# ADC_AK5572.net
KiCad netlist of a schematic drawn in Altium Designer
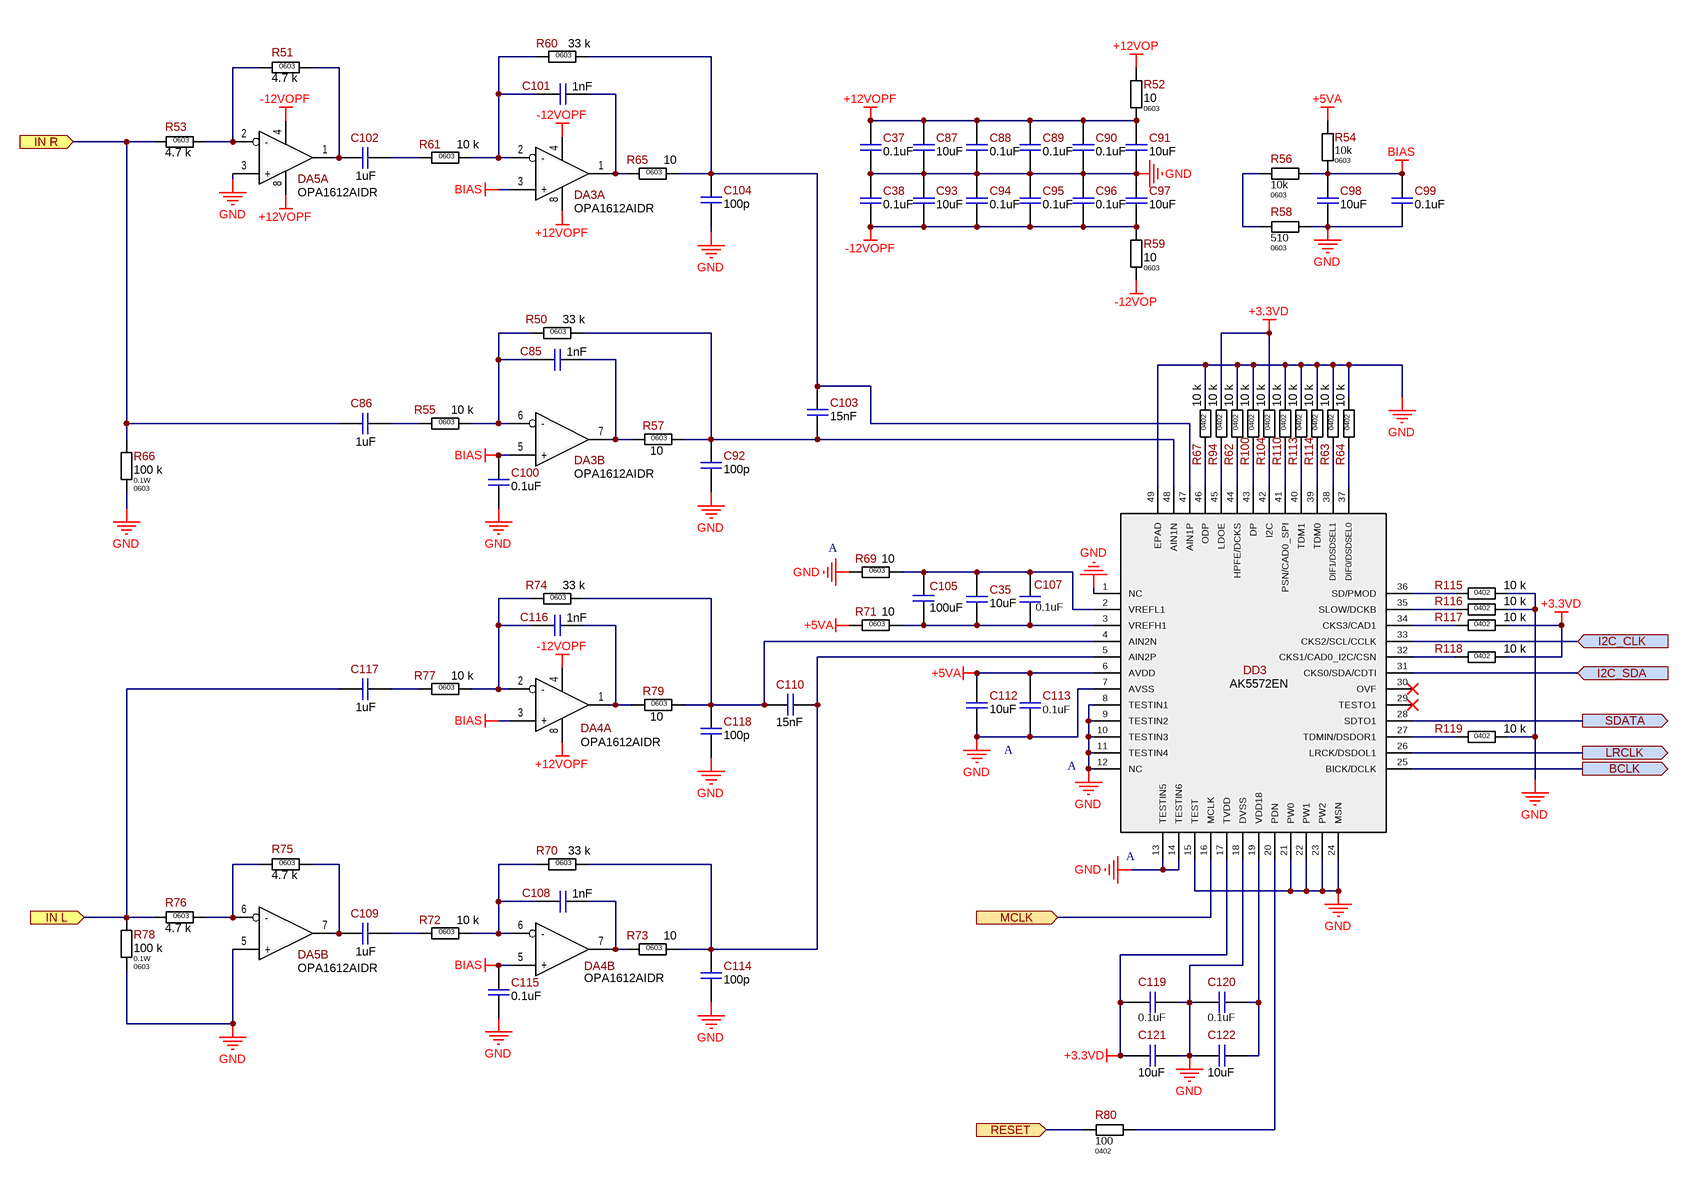
[diagram p0: ADC_AK5572.SchDoc]

(export (version "E")
  (design (tool "Eeschema 10.0.6"))
  (components
    (comp (ref "C35")
      (value "10uF")
      (footprint "C0402(1005)")
      (description "CAP CER 10UF 6.3V X6S 0402")
      (fields (field (name "PART NUMBER") "10uF  6.3V C0402") (field (name "TOLERANCE") "±20%"))
      (libsource (lib "Database") (part "Capacitor_Ceramic"))
    )
    (comp (ref "C37")
      (value "0.1uF")
      (footprint "C0603(1608)")
      (description "CAP CER 0.1UF 50V X7R 0603")
      (fields (field (name "PART NUMBER") "0.1uF  50V C0603") (field (name "TOLERANCE") "±10%"))
      (libsource (lib "Database") (part "Capacitor_Ceramic"))
    )
    (comp (ref "C38")
      (value "0.1uF")
      (footprint "C0603(1608)")
      (description "CAP CER 0.1UF 50V X7R 0603")
      (fields (field (name "PART NUMBER") "0.1uF  50V C0603") (field (name "TOLERANCE") "±10%"))
      (libsource (lib "Database") (part "Capacitor_Ceramic"))
    )
    (comp (ref "C85")
      (value "1nF")
      (footprint "C0603(1608)")
      (description "CAP CER 1nF 25V X7R 0603")
      (fields (field (name "PART NUMBER") "1nF  25V C0603") (field (name "TOLERANCE") "±10%"))
      (libsource (lib "Database") (part "Capacitor_Ceramic"))
    )
    (comp (ref "C86")
      (value "1uF")
      (footprint "WIMA5")
      (description "CAP FILM 1UF 10% 100VDC")
      (fields
        (field (name "PART NUMBER") "1uF  30В AC, 50В DC 5.5x10x7, 2мм")
        (field (name "TOLERANCE") "±10%")
      )
      (libsource (lib "Database") (part "Capacitor_Ceramic"))
    )
    (comp (ref "C87")
      (value "10uF")
      (footprint "C0603(1608)")
      (description "CAP CER 10UF 35V X5R 0603")
      (fields (field (name "PART NUMBER") "10uF  35V C0603") (field (name "TOLERANCE") "±20%"))
      (libsource (lib "Database") (part "Capacitor_Ceramic"))
    )
    (comp (ref "C88")
      (value "0.1uF")
      (footprint "C0603(1608)")
      (description "CAP CER 0.1UF 50V X7R 0603")
      (fields (field (name "PART NUMBER") "0.1uF  50V C0603") (field (name "TOLERANCE") "±10%"))
      (libsource (lib "Database") (part "Capacitor_Ceramic"))
    )
    (comp (ref "C89")
      (value "0.1uF")
      (footprint "C0603(1608)")
      (description "CAP CER 0.1UF 50V X7R 0603")
      (fields (field (name "PART NUMBER") "0.1uF  50V C0603") (field (name "TOLERANCE") "±10%"))
      (libsource (lib "Database") (part "Capacitor_Ceramic"))
    )
    (comp (ref "C90")
      (value "0.1uF")
      (footprint "C0603(1608)")
      (description "CAP CER 0.1UF 50V X7R 0603")
      (fields (field (name "PART NUMBER") "0.1uF  50V C0603") (field (name "TOLERANCE") "±10%"))
      (libsource (lib "Database") (part "Capacitor_Ceramic"))
    )
    (comp (ref "C91")
      (value "10uF")
      (footprint "C0603(1608)")
      (description "CAP CER 10UF 35V X5R 0603")
      (fields (field (name "PART NUMBER") "10uF  35V C0603") (field (name "TOLERANCE") "±20%"))
      (libsource (lib "Database") (part "Capacitor_Ceramic"))
    )
    (comp (ref "C92")
      (value "100p")
      (footprint "C0603(1608)")
      (description "CAP CER 0.1UF 50V X7R 0603")
      (fields (field (name "PART NUMBER") "0.1uF  50V C0603") (field (name "TOLERANCE") "±10%"))
      (libsource (lib "Database") (part "Capacitor_Ceramic"))
    )
    (comp (ref "C93")
      (value "10uF")
      (footprint "C0603(1608)")
      (description "CAP CER 10UF 35V X5R 0603")
      (fields (field (name "PART NUMBER") "10uF  35V C0603") (field (name "TOLERANCE") "±20%"))
      (libsource (lib "Database") (part "Capacitor_Ceramic"))
    )
    (comp (ref "C94")
      (value "0.1uF")
      (footprint "C0603(1608)")
      (description "CAP CER 0.1UF 50V X7R 0603")
      (fields (field (name "PART NUMBER") "0.1uF  50V C0603") (field (name "TOLERANCE") "±10%"))
      (libsource (lib "Database") (part "Capacitor_Ceramic"))
    )
    (comp (ref "C95")
      (value "0.1uF")
      (footprint "C0603(1608)")
      (description "CAP CER 0.1UF 50V X7R 0603")
      (fields (field (name "PART NUMBER") "0.1uF  50V C0603") (field (name "TOLERANCE") "±10%"))
      (libsource (lib "Database") (part "Capacitor_Ceramic"))
    )
    (comp (ref "C96")
      (value "0.1uF")
      (footprint "C0603(1608)")
      (description "CAP CER 0.1UF 50V X7R 0603")
      (fields (field (name "PART NUMBER") "0.1uF  50V C0603") (field (name "TOLERANCE") "±10%"))
      (libsource (lib "Database") (part "Capacitor_Ceramic"))
    )
    (comp (ref "C97")
      (value "10uF")
      (footprint "C0603(1608)")
      (description "CAP CER 10UF 35V X5R 0603")
      (fields (field (name "PART NUMBER") "10uF  35V C0603") (field (name "TOLERANCE") "±20%"))
      (libsource (lib "Database") (part "Capacitor_Ceramic"))
    )
    (comp (ref "C98")
      (value "10uF")
      (footprint "C0603(1608)")
      (description "CAP CER 10UF 35V X5R 0603")
      (fields (field (name "PART NUMBER") "10uF  35V C0603") (field (name "TOLERANCE") "±20%"))
      (libsource (lib "Database") (part "Capacitor_Ceramic"))
    )
    (comp (ref "C99")
      (value "0.1uF")
      (footprint "C0603(1608)")
      (description "CAP CER 0.1UF 50V X7R 0603")
      (fields (field (name "PART NUMBER") "0.1uF  50V C0603") (field (name "TOLERANCE") "±10%"))
      (libsource (lib "Database") (part "Capacitor_Ceramic"))
    )
    (comp (ref "C100")
      (value "0.1uF")
      (footprint "C0603(1608)")
      (description "CAP CER 0.1UF 50V X7R 0603")
      (fields (field (name "PART NUMBER") "0.1uF  50V C0603") (field (name "TOLERANCE") "±10%"))
      (libsource (lib "Database") (part "Capacitor_Ceramic"))
    )
    (comp (ref "C101")
      (value "1nF")
      (footprint "C0603(1608)")
      (description "CAP CER 1nF 25V X7R 0603")
      (fields (field (name "PART NUMBER") "1nF  25V C0603") (field (name "TOLERANCE") "±10%"))
      (libsource (lib "Database") (part "Capacitor_Ceramic"))
    )
    (comp (ref "C102")
      (value "1uF")
      (footprint "WIMA5")
      (description "CAP FILM 1UF 10% 100VDC")
      (fields
        (field (name "PART NUMBER") "1uF  30В AC, 50В DC 5.5x10x7, 2мм")
        (field (name "TOLERANCE") "±10%")
      )
      (libsource (lib "Database") (part "Capacitor_Ceramic"))
    )
    (comp (ref "C103")
      (value "15nF")
      (footprint "C0402(1005)")
      (description "CAP CER NPO 15nF 25V")
      (fields (field (name "PART NUMBER") "15nF  25V C0402") (field (name "TOLERANCE") "10%"))
      (libsource (lib "Database") (part "Capacitor_Ceramic"))
    )
    (comp (ref "C104")
      (value "100p")
      (footprint "C0603(1608)")
      (description "CAP CER 0.1UF 50V X7R 0603")
      (fields (field (name "PART NUMBER") "0.1uF  50V C0603") (field (name "TOLERANCE") "±10%"))
      (libsource (lib "Database") (part "Capacitor_Ceramic"))
    )
    (comp (ref "C105")
      (value "100uF")
      (footprint "C1206(3216)")
      (description "CAP CER 100UF 10V X5T 1206")
      (fields (field (name "PART NUMBER") "100uF  10V С1206") (field (name "TOLERANCE") "±20%"))
      (libsource (lib "Database") (part "Capacitor_Ceramic"))
    )
    (comp (ref "C107")
      (value "0.1uF")
      (footprint "C0402(1005)")
      (description "CAP CER 0.1UF 25V X7R 0603")
      (fields (field (name "PART NUMBER") "0.1uF  25V C0403") (field (name "TOLERANCE") "±10%"))
      (libsource (lib "Database") (part "Capacitor_Ceramic"))
    )
    (comp (ref "C108")
      (value "1nF")
      (footprint "C0603(1608)")
      (description "CAP CER 1nF 25V X7R 0603")
      (fields (field (name "PART NUMBER") "1nF  25V C0603") (field (name "TOLERANCE") "±10%"))
      (libsource (lib "Database") (part "Capacitor_Ceramic"))
    )
    (comp (ref "C109")
      (value "1uF")
      (footprint "WIMA5")
      (description "CAP FILM 1UF 10% 100VDC")
      (fields
        (field (name "PART NUMBER") "1uF  30В AC, 50В DC 5.5x10x7, 2мм")
        (field (name "TOLERANCE") "±10%")
      )
      (libsource (lib "Database") (part "Capacitor_Ceramic"))
    )
    (comp (ref "C110")
      (value "15nF")
      (footprint "C0402(1005)")
      (description "CAP CER NPO 15nF 25V")
      (fields (field (name "PART NUMBER") "15nF  25V C0402") (field (name "TOLERANCE") "10%"))
      (libsource (lib "Database") (part "Capacitor_Ceramic"))
    )
    (comp (ref "C112")
      (value "10uF")
      (footprint "C0402(1005)")
      (description "CAP CER 10UF 6.3V X6S 0402")
      (fields (field (name "PART NUMBER") "10uF  6.3V C0402") (field (name "TOLERANCE") "±20%"))
      (libsource (lib "Database") (part "Capacitor_Ceramic"))
    )
    (comp (ref "C113")
      (value "0.1uF")
      (footprint "C0402(1005)")
      (description "CAP CER 0.1UF 25V X7R 0603")
      (fields (field (name "PART NUMBER") "0.1uF  25V C0403") (field (name "TOLERANCE") "±10%"))
      (libsource (lib "Database") (part "Capacitor_Ceramic"))
    )
    (comp (ref "C114")
      (value "100p")
      (footprint "C0603(1608)")
      (description "CAP CER 0.1UF 50V X7R 0603")
      (fields (field (name "PART NUMBER") "0.1uF  50V C0603") (field (name "TOLERANCE") "±10%"))
      (libsource (lib "Database") (part "Capacitor_Ceramic"))
    )
    (comp (ref "C115")
      (value "0.1uF")
      (footprint "C0603(1608)")
      (description "CAP CER 0.1UF 50V X7R 0603")
      (fields (field (name "PART NUMBER") "0.1uF  50V C0603") (field (name "TOLERANCE") "±10%"))
      (libsource (lib "Database") (part "Capacitor_Ceramic"))
    )
    (comp (ref "C116")
      (value "1nF")
      (footprint "C0603(1608)")
      (description "CAP CER 1nF 25V X7R 0603")
      (fields (field (name "PART NUMBER") "1nF  25V C0603") (field (name "TOLERANCE") "±10%"))
      (libsource (lib "Database") (part "Capacitor_Ceramic"))
    )
    (comp (ref "C117")
      (value "1uF")
      (footprint "WIMA5")
      (description "CAP FILM 1UF 10% 100VDC")
      (fields
        (field (name "PART NUMBER") "1uF  30В AC, 50В DC 5.5x10x7, 2мм")
        (field (name "TOLERANCE") "±10%")
      )
      (libsource (lib "Database") (part "Capacitor_Ceramic"))
    )
    (comp (ref "C118")
      (value "100p")
      (footprint "C0603(1608)")
      (description "CAP CER 0.1UF 50V X7R 0603")
      (fields (field (name "PART NUMBER") "0.1uF  50V C0603") (field (name "TOLERANCE") "±10%"))
      (libsource (lib "Database") (part "Capacitor_Ceramic"))
    )
    (comp (ref "C119")
      (value "0.1uF")
      (footprint "C0402(1005)")
      (description "CAP CER 0.1UF 25V X7R 0603")
      (fields (field (name "PART NUMBER") "0.1uF  25V C0403") (field (name "TOLERANCE") "±10%"))
      (libsource (lib "Database") (part "Capacitor_Ceramic"))
    )
    (comp (ref "C120")
      (value "0.1uF")
      (footprint "C0402(1005)")
      (description "CAP CER 0.1UF 25V X7R 0603")
      (fields (field (name "PART NUMBER") "0.1uF  25V C0403") (field (name "TOLERANCE") "±10%"))
      (libsource (lib "Database") (part "Capacitor_Ceramic"))
    )
    (comp (ref "C121")
      (value "10uF")
      (footprint "C0402(1005)")
      (description "CAP CER 10UF 6.3V X6S 0402")
      (fields (field (name "PART NUMBER") "10uF  6.3V C0402") (field (name "TOLERANCE") "±20%"))
      (libsource (lib "Database") (part "Capacitor_Ceramic"))
    )
    (comp (ref "C122")
      (value "10uF")
      (footprint "C0402(1005)")
      (description "CAP CER 10UF 6.3V X6S 0402")
      (fields (field (name "PART NUMBER") "10uF  6.3V C0402") (field (name "TOLERANCE") "±20%"))
      (libsource (lib "Database") (part "Capacitor_Ceramic"))
    )
    (comp (ref "DA3")
      (value "OPA1612AIDR")
      (footprint "SOIC8")
      (description "Audio Amplifier 2 Circuit Rail-to-Rail 8-SOIC")
      (fields (field (name "MANUFACTURER") "Texas Instruments"))
      (libsource (lib "Database") (part "AMP8"))
    )
    (comp (ref "DA4")
      (value "OPA1612AIDR")
      (footprint "SOIC8")
      (description "Audio Amplifier 2 Circuit Rail-to-Rail 8-SOIC")
      (fields (field (name "MANUFACTURER") "Texas Instruments"))
      (libsource (lib "Database") (part "AMP8"))
    )
    (comp (ref "DA5")
      (value "OPA1612AIDR")
      (footprint "SOIC8")
      (description "Audio Amplifier 2 Circuit Rail-to-Rail 8-SOIC")
      (fields (field (name "MANUFACTURER") "Texas Instruments"))
      (libsource (lib "Database") (part "AMP8"))
    )
    (comp (ref "DD3")
      (value "AK5572EN")
      (footprint "QFN50P700X700X60-49N")
      (description "ADC, Audio 32 b 768k DSD, I2S 48-QFN (7x7)")
      (fields (field (name "MANUFACTURER") "Asahi Kasei Microdevices/AKM"))
      (libsource (lib "Database") (part "AK5572EN"))
    )
    (comp (ref "R50")
      (value "33 k")
      (footprint "R0603")
      (description "RES SMD 33 k OHM  ±1% 1/10W 0603")
      (fields
        (field (name "PACKAGE/CASE") "0603")
        (field (name "PART NUMBER") "33 k  R0603")
        (field (name "TOLERANCE") "±1%")
      )
      (libsource (lib "Database") (part "R0603"))
    )
    (comp (ref "R51")
      (value "4.7 k")
      (footprint "R0603")
      (description "RES SMD 4.7 k OHM  ±1% 1/10W 0603")
      (fields
        (field (name "PACKAGE/CASE") "0603")
        (field (name "PART NUMBER") "4.7 k  R0603")
        (field (name "TOLERANCE") "±1%")
      )
      (libsource (lib "Database") (part "R0603"))
    )
    (comp (ref "R52")
      (value "10")
      (footprint "R0603")
      (description "RES SMD 10 OHM  ±1% 1/10W 0603")
      (fields
        (field (name "PACKAGE/CASE") "0603")
        (field (name "PART NUMBER") "10  R0603")
        (field (name "TOLERANCE") "±1%")
      )
      (libsource (lib "Database") (part "R0603"))
    )
    (comp (ref "R53")
      (value "4.7 k")
      (footprint "R0603")
      (description "RES SMD 4.7 k OHM  ±1% 1/10W 0603")
      (fields
        (field (name "PACKAGE/CASE") "0603")
        (field (name "PART NUMBER") "4.7 k  R0603")
        (field (name "TOLERANCE") "±1%")
      )
      (libsource (lib "Database") (part "R0603"))
    )
    (comp (ref "R54")
      (value "10k")
      (footprint "R0603")
      (description "RES SMD 10 k OHM  ±1% 1/10W 0603")
      (fields
        (field (name "PACKAGE/CASE") "0603")
        (field (name "PART NUMBER") "10 k  R0603")
        (field (name "TOLERANCE") "±1%")
      )
      (libsource (lib "Database") (part "R0603"))
    )
    (comp (ref "R55")
      (value "10 k")
      (footprint "R0603")
      (description "RES SMD 10 k OHM  ±1% 1/10W 0603")
      (fields
        (field (name "PACKAGE/CASE") "0603")
        (field (name "PART NUMBER") "10 k  R0603")
        (field (name "TOLERANCE") "±1%")
      )
      (libsource (lib "Database") (part "R0603"))
    )
    (comp (ref "R56")
      (value "10k")
      (footprint "R0603")
      (description "RES SMD 10 k OHM  ±1% 1/10W 0603")
      (fields
        (field (name "PACKAGE/CASE") "0603")
        (field (name "PART NUMBER") "10 k  R0603")
        (field (name "TOLERANCE") "±1%")
      )
      (libsource (lib "Database") (part "R0603"))
    )
    (comp (ref "R57")
      (value "10")
      (footprint "R0603")
      (description "RES SMD 10 OHM  ±1% 1/10W 0603")
      (fields
        (field (name "PACKAGE/CASE") "0603")
        (field (name "PART NUMBER") "10  R0603")
        (field (name "TOLERANCE") "±1%")
      )
      (libsource (lib "Database") (part "R0603"))
    )
    (comp (ref "R58")
      (value "510")
      (footprint "R0603")
      (description "RES SMD 10 k OHM  ±1% 1/10W 0603")
      (fields
        (field (name "PACKAGE/CASE") "0603")
        (field (name "PART NUMBER") "10 k  R0603")
        (field (name "TOLERANCE") "±1%")
      )
      (libsource (lib "Database") (part "R0603"))
    )
    (comp (ref "R59")
      (value "10")
      (footprint "R0603")
      (description "RES SMD 10 OHM  ±1% 1/10W 0603")
      (fields
        (field (name "PACKAGE/CASE") "0603")
        (field (name "PART NUMBER") "10  R0603")
        (field (name "TOLERANCE") "±1%")
      )
      (libsource (lib "Database") (part "R0603"))
    )
    (comp (ref "R60")
      (value "33 k")
      (footprint "R0603")
      (description "RES SMD 33 k OHM  ±1% 1/10W 0603")
      (fields
        (field (name "PACKAGE/CASE") "0603")
        (field (name "PART NUMBER") "33 k  R0603")
        (field (name "TOLERANCE") "±1%")
      )
      (libsource (lib "Database") (part "R0603"))
    )
    (comp (ref "R61")
      (value "10 k")
      (footprint "R0603")
      (description "RES SMD 10 k OHM  ±1% 1/10W 0603")
      (fields
        (field (name "PACKAGE/CASE") "0603")
        (field (name "PART NUMBER") "10 k  R0603")
        (field (name "TOLERANCE") "±1%")
      )
      (libsource (lib "Database") (part "R0603"))
    )
    (comp (ref "R62")
      (value "10 k")
      (footprint "R0402")
      (description "RES SMD 10 k OHM  ±1% 1/16W 0402")
      (fields
        (field (name "PACKAGE/CASE") "0402")
        (field (name "PART NUMBER") "10 k  R0402")
        (field (name "TOLERANCE") "±1%")
      )
      (libsource (lib "Database") (part "R0402"))
    )
    (comp (ref "R63")
      (value "10 k")
      (footprint "R0402")
      (description "RES SMD 10 k OHM  ±1% 1/16W 0402")
      (fields
        (field (name "PACKAGE/CASE") "0402")
        (field (name "PART NUMBER") "10 k  R0402")
        (field (name "TOLERANCE") "±1%")
      )
      (libsource (lib "Database") (part "R0402"))
    )
    (comp (ref "R64")
      (value "10 k")
      (footprint "R0402")
      (description "RES SMD 10 k OHM  ±1% 1/16W 0402")
      (fields
        (field (name "PACKAGE/CASE") "0402")
        (field (name "PART NUMBER") "10 k  R0402")
        (field (name "TOLERANCE") "±1%")
      )
      (libsource (lib "Database") (part "R0402"))
    )
    (comp (ref "R65")
      (value "10")
      (footprint "R0603")
      (description "RES SMD 10 OHM  ±1% 1/10W 0603")
      (fields
        (field (name "PACKAGE/CASE") "0603")
        (field (name "PART NUMBER") "10  R0603")
        (field (name "TOLERANCE") "±1%")
      )
      (libsource (lib "Database") (part "R0603"))
    )
    (comp (ref "R66")
      (value "100 k")
      (footprint "R0603")
      (description "RES SMD 100 k OHM  ±1% 1/10W 0603")
      (fields
        (field (name "POWER RATING") "0.1W")
        (field (name "PACKAGE/CASE") "0603")
        (field (name "PART NUMBER") "100 k  R0603")
        (field (name "TOLERANCE") "±1%")
      )
      (libsource (lib "Database") (part "R0603"))
    )
    (comp (ref "R67")
      (value "10 k")
      (footprint "R0402")
      (description "RES SMD 10 k OHM  ±1% 1/16W 0402")
      (fields
        (field (name "PACKAGE/CASE") "0402")
        (field (name "PART NUMBER") "10 k  R0402")
        (field (name "TOLERANCE") "±1%")
      )
      (libsource (lib "Database") (part "R0402"))
    )
    (comp (ref "R69")
      (value "10")
      (footprint "R0603")
      (description "RES SMD 10 OHM  ±1% 1/10W 0603")
      (fields
        (field (name "PACKAGE/CASE") "0603")
        (field (name "PART NUMBER") "10  R0603")
        (field (name "TOLERANCE") "±1%")
      )
      (libsource (lib "Database") (part "R0603"))
    )
    (comp (ref "R70")
      (value "33 k")
      (footprint "R0603")
      (description "RES SMD 33 k OHM  ±1% 1/10W 0603")
      (fields
        (field (name "PACKAGE/CASE") "0603")
        (field (name "PART NUMBER") "33 k  R0603")
        (field (name "TOLERANCE") "±1%")
      )
      (libsource (lib "Database") (part "R0603"))
    )
    (comp (ref "R71")
      (value "10")
      (footprint "R0603")
      (description "RES SMD 10 OHM  ±1% 1/10W 0603")
      (fields
        (field (name "PACKAGE/CASE") "0603")
        (field (name "PART NUMBER") "10  R0603")
        (field (name "TOLERANCE") "±1%")
      )
      (libsource (lib "Database") (part "R0603"))
    )
    (comp (ref "R72")
      (value "10 k")
      (footprint "R0603")
      (description "RES SMD 10 k OHM  ±1% 1/10W 0603")
      (fields
        (field (name "PACKAGE/CASE") "0603")
        (field (name "PART NUMBER") "10 k  R0603")
        (field (name "TOLERANCE") "±1%")
      )
      (libsource (lib "Database") (part "R0603"))
    )
    (comp (ref "R73")
      (value "10")
      (footprint "R0603")
      (description "RES SMD 10 OHM  ±1% 1/10W 0603")
      (fields
        (field (name "PACKAGE/CASE") "0603")
        (field (name "PART NUMBER") "10  R0603")
        (field (name "TOLERANCE") "±1%")
      )
      (libsource (lib "Database") (part "R0603"))
    )
    (comp (ref "R74")
      (value "33 k")
      (footprint "R0603")
      (description "RES SMD 33 k OHM  ±1% 1/10W 0603")
      (fields
        (field (name "PACKAGE/CASE") "0603")
        (field (name "PART NUMBER") "33 k  R0603")
        (field (name "TOLERANCE") "±1%")
      )
      (libsource (lib "Database") (part "R0603"))
    )
    (comp (ref "R75")
      (value "4.7 k")
      (footprint "R0603")
      (description "RES SMD 4.7 k OHM  ±1% 1/10W 0603")
      (fields
        (field (name "PACKAGE/CASE") "0603")
        (field (name "PART NUMBER") "4.7 k  R0603")
        (field (name "TOLERANCE") "±1%")
      )
      (libsource (lib "Database") (part "R0603"))
    )
    (comp (ref "R76")
      (value "4.7 k")
      (footprint "R0603")
      (description "RES SMD 4.7 k OHM  ±1% 1/10W 0603")
      (fields
        (field (name "PACKAGE/CASE") "0603")
        (field (name "PART NUMBER") "4.7 k  R0603")
        (field (name "TOLERANCE") "±1%")
      )
      (libsource (lib "Database") (part "R0603"))
    )
    (comp (ref "R77")
      (value "10 k")
      (footprint "R0603")
      (description "RES SMD 10 k OHM  ±1% 1/10W 0603")
      (fields
        (field (name "PACKAGE/CASE") "0603")
        (field (name "PART NUMBER") "10 k  R0603")
        (field (name "TOLERANCE") "±1%")
      )
      (libsource (lib "Database") (part "R0603"))
    )
    (comp (ref "R78")
      (value "100 k")
      (footprint "R0603")
      (description "RES SMD 100 k OHM  ±1% 1/10W 0603")
      (fields
        (field (name "POWER RATING") "0.1W")
        (field (name "PACKAGE/CASE") "0603")
        (field (name "PART NUMBER") "100 k  R0603")
        (field (name "TOLERANCE") "±1%")
      )
      (libsource (lib "Database") (part "R0603"))
    )
    (comp (ref "R79")
      (value "10")
      (footprint "R0603")
      (description "RES SMD 10 OHM  ±1% 1/10W 0603")
      (fields
        (field (name "PACKAGE/CASE") "0603")
        (field (name "PART NUMBER") "10  R0603")
        (field (name "TOLERANCE") "±1%")
      )
      (libsource (lib "Database") (part "R0603"))
    )
    (comp (ref "R80")
      (value "100")
      (footprint "R0402")
      (description "RES SMD 100 OHM  ±1% 1/16W 0402")
      (fields
        (field (name "PACKAGE/CASE") "0402")
        (field (name "PART NUMBER") "100  R0402")
        (field (name "TOLERANCE") "±1%")
      )
      (libsource (lib "Database") (part "R0402"))
    )
    (comp (ref "R94")
      (value "10 k")
      (footprint "R0402")
      (description "RES SMD 10 k OHM  ±1% 1/16W 0402")
      (fields
        (field (name "PACKAGE/CASE") "0402")
        (field (name "PART NUMBER") "10 k  R0402")
        (field (name "TOLERANCE") "±1%")
      )
      (libsource (lib "Database") (part "R0402"))
    )
    (comp (ref "R100")
      (value "10 k")
      (footprint "R0402")
      (description "RES SMD 10 k OHM  ±1% 1/16W 0402")
      (fields
        (field (name "PACKAGE/CASE") "0402")
        (field (name "PART NUMBER") "10 k  R0402")
        (field (name "TOLERANCE") "±1%")
      )
      (libsource (lib "Database") (part "R0402"))
    )
    (comp (ref "R104")
      (value "10 k")
      (footprint "R0402")
      (description "RES SMD 10 k OHM  ±1% 1/16W 0402")
      (fields
        (field (name "PACKAGE/CASE") "0402")
        (field (name "PART NUMBER") "10 k  R0402")
        (field (name "TOLERANCE") "±1%")
      )
      (libsource (lib "Database") (part "R0402"))
    )
    (comp (ref "R110")
      (value "10 k")
      (footprint "R0402")
      (description "RES SMD 10 k OHM  ±1% 1/16W 0402")
      (fields
        (field (name "PACKAGE/CASE") "0402")
        (field (name "PART NUMBER") "10 k  R0402")
        (field (name "TOLERANCE") "±1%")
      )
      (libsource (lib "Database") (part "R0402"))
    )
    (comp (ref "R113")
      (value "10 k")
      (footprint "R0402")
      (description "RES SMD 10 k OHM  ±1% 1/16W 0402")
      (fields
        (field (name "PACKAGE/CASE") "0402")
        (field (name "PART NUMBER") "10 k  R0402")
        (field (name "TOLERANCE") "±1%")
      )
      (libsource (lib "Database") (part "R0402"))
    )
    (comp (ref "R114")
      (value "10 k")
      (footprint "R0402")
      (description "RES SMD 10 k OHM  ±1% 1/16W 0402")
      (fields
        (field (name "PACKAGE/CASE") "0402")
        (field (name "PART NUMBER") "10 k  R0402")
        (field (name "TOLERANCE") "±1%")
      )
      (libsource (lib "Database") (part "R0402"))
    )
    (comp (ref "R115")
      (value "10 k")
      (footprint "R0402")
      (description "RES SMD 10 k OHM  ±1% 1/16W 0402")
      (fields
        (field (name "PACKAGE/CASE") "0402")
        (field (name "PART NUMBER") "10 k  R0402")
        (field (name "TOLERANCE") "±1%")
      )
      (libsource (lib "Database") (part "R0402"))
    )
    (comp (ref "R116")
      (value "10 k")
      (footprint "R0402")
      (description "RES SMD 10 k OHM  ±1% 1/16W 0402")
      (fields
        (field (name "PACKAGE/CASE") "0402")
        (field (name "PART NUMBER") "10 k  R0402")
        (field (name "TOLERANCE") "±1%")
      )
      (libsource (lib "Database") (part "R0402"))
    )
    (comp (ref "R117")
      (value "10 k")
      (footprint "R0402")
      (description "RES SMD 10 k OHM  ±1% 1/16W 0402")
      (fields
        (field (name "PACKAGE/CASE") "0402")
        (field (name "PART NUMBER") "10 k  R0402")
        (field (name "TOLERANCE") "±1%")
      )
      (libsource (lib "Database") (part "R0402"))
    )
    (comp (ref "R118")
      (value "10 k")
      (footprint "R0402")
      (description "RES SMD 10 k OHM  ±1% 1/16W 0402")
      (fields
        (field (name "PACKAGE/CASE") "0402")
        (field (name "PART NUMBER") "10 k  R0402")
        (field (name "TOLERANCE") "±1%")
      )
      (libsource (lib "Database") (part "R0402"))
    )
    (comp (ref "R119")
      (value "10 k")
      (footprint "R0402")
      (description "RES SMD 10 k OHM  ±1% 1/16W 0402")
      (fields
        (field (name "PACKAGE/CASE") "0402")
        (field (name "PART NUMBER") "10 k  R0402")
        (field (name "TOLERANCE") "±1%")
      )
      (libsource (lib "Database") (part "R0402"))
    )
  )
  (nets
    (net (code "1") (name "+3.3VD") (class "Default")
      (node (ref "C119") (pin "2") (pinfunction "2_2") (pintype "passive"))
      (node (ref "C121") (pin "2") (pinfunction "2_2") (pintype "passive"))
      (node (ref "DD3") (pin "17") (pinfunction "TVDD_17") (pintype "passive"))
      (node (ref "R104") (pin "2") (pinfunction "2_2") (pintype "passive"))
      (node (ref "R117") (pin "1") (pinfunction "1_1") (pintype "passive"))
      (node (ref "R118") (pin "1") (pinfunction "1_1") (pintype "passive"))
      (node (ref "R94") (pin "2") (pinfunction "2_2") (pintype "passive"))
    )
    (net (code "2") (name "+5VA") (class "Default")
      (node (ref "C112") (pin "2") (pinfunction "2_2") (pintype "passive"))
      (node (ref "C113") (pin "2") (pinfunction "2_2") (pintype "passive"))
      (node (ref "DD3") (pin "6") (pinfunction "AVDD_6") (pintype "passive"))
      (node (ref "R54") (pin "1") (pinfunction "1_1") (pintype "passive"))
      (node (ref "R71") (pin "2") (pinfunction "2_2") (pintype "passive"))
    )
    (net (code "3") (name "+12VOP") (class "Default")
      (node (ref "R52") (pin "1") (pinfunction "1_1") (pintype "passive"))
    )
    (net (code "4") (name "+12VOPF") (class "Default")
      (node (ref "C37") (pin "2") (pinfunction "2_2") (pintype "passive"))
      (node (ref "C87") (pin "2") (pinfunction "2_2") (pintype "passive"))
      (node (ref "C88") (pin "2") (pinfunction "2_2") (pintype "passive"))
      (node (ref "C89") (pin "2") (pinfunction "2_2") (pintype "passive"))
      (node (ref "C90") (pin "2") (pinfunction "2_2") (pintype "passive"))
      (node (ref "C91") (pin "2") (pinfunction "2_2") (pintype "passive"))
      (node (ref "DA3") (pin "8") (pinfunction "V+_8") (pintype "passive"))
      (node (ref "DA4") (pin "8") (pinfunction "V+_8") (pintype "passive"))
      (node (ref "DA5") (pin "8") (pinfunction "V+_8") (pintype "passive"))
      (node (ref "R52") (pin "2") (pinfunction "2_2") (pintype "passive"))
    )
    (net (code "5") (name "-12VOP") (class "Default")
      (node (ref "R59") (pin "2") (pinfunction "2_2") (pintype "passive"))
    )
    (net (code "6") (name "-12VOPF") (class "Default")
      (node (ref "C38") (pin "1") (pinfunction "1_1") (pintype "passive"))
      (node (ref "C93") (pin "1") (pinfunction "1_1") (pintype "passive"))
      (node (ref "C94") (pin "1") (pinfunction "1_1") (pintype "passive"))
      (node (ref "C95") (pin "1") (pinfunction "1_1") (pintype "passive"))
      (node (ref "C96") (pin "1") (pinfunction "1_1") (pintype "passive"))
      (node (ref "C97") (pin "1") (pinfunction "1_1") (pintype "passive"))
      (node (ref "DA3") (pin "4") (pinfunction "V-_4") (pintype "passive"))
      (node (ref "DA4") (pin "4") (pinfunction "V-_4") (pintype "passive"))
      (node (ref "DA5") (pin "4") (pinfunction "V-_4") (pintype "passive"))
      (node (ref "R59") (pin "1") (pinfunction "1_1") (pintype "passive"))
    )
    (net (code "7") (name "/BCLK") (class "Default")
      (node (ref "DD3") (pin "25") (pinfunction "BICK/DCLK_25") (pintype "passive"))
    )
    (net (code "8") (name "/I2C_CLK") (class "Default")
      (node (ref "DD3") (pin "33") (pinfunction "CKS2/SCL/CCLK_33") (pintype "passive"))
    )
    (net (code "9") (name "/I2C_SDA") (class "Default")
      (node (ref "DD3") (pin "31") (pinfunction "CKS0/SDA/CDTI_31") (pintype "passive"))
    )
    (net (code "10") (name "/IN L") (class "Default")
      (node (ref "C117") (pin "1") (pinfunction "1_1") (pintype "passive"))
      (node (ref "R76") (pin "2") (pinfunction "2_2") (pintype "passive"))
      (node (ref "R78") (pin "2") (pinfunction "2_2") (pintype "passive"))
    )
    (net (code "11") (name "/IN R") (class "Default")
      (node (ref "C86") (pin "1") (pinfunction "1_1") (pintype "passive"))
      (node (ref "R53") (pin "2") (pinfunction "2_2") (pintype "passive"))
      (node (ref "R66") (pin "2") (pinfunction "2_2") (pintype "passive"))
    )
    (net (code "12") (name "/LRCLK") (class "Default")
      (node (ref "DD3") (pin "26") (pinfunction "LRCK/DSDOL1_26") (pintype "passive"))
    )
    (net (code "13") (name "/MCLK") (class "Default")
      (node (ref "DD3") (pin "16") (pinfunction "MCLK_16") (pintype "passive"))
    )
    (net (code "14") (name "/RESET") (class "Default")
      (node (ref "R80") (pin "1") (pinfunction "1_1") (pintype "passive"))
    )
    (net (code "15") (name "/SDATA") (class "Default")
      (node (ref "DD3") (pin "28") (pinfunction "SDTO1_28") (pintype "passive"))
    )
    (net (code "16") (name "BIAS") (class "Default")
      (node (ref "C100") (pin "2") (pinfunction "2_2") (pintype "passive"))
      (node (ref "C115") (pin "2") (pinfunction "2_2") (pintype "passive"))
      (node (ref "C98") (pin "2") (pinfunction "2_2") (pintype "passive"))
      (node (ref "C99") (pin "2") (pinfunction "2_2") (pintype "passive"))
      (node (ref "DA3") (pin "3") (pinfunction "+_3") (pintype "passive"))
      (node (ref "DA3") (pin "5") (pinfunction "+_5") (pintype "passive"))
      (node (ref "DA4") (pin "3") (pinfunction "+_3") (pintype "passive"))
      (node (ref "DA4") (pin "5") (pinfunction "+_5") (pintype "passive"))
      (node (ref "R54") (pin "2") (pinfunction "2_2") (pintype "passive"))
      (node (ref "R56") (pin "2") (pinfunction "2_2") (pintype "passive"))
    )
    (net (code "17") (name "GND") (class "Default")
      (node (ref "C100") (pin "1") (pinfunction "1_1") (pintype "passive"))
      (node (ref "C104") (pin "2") (pinfunction "2_2") (pintype "passive"))
      (node (ref "C112") (pin "1") (pinfunction "1_1") (pintype "passive"))
      (node (ref "C113") (pin "1") (pinfunction "1_1") (pintype "passive"))
      (node (ref "C114") (pin "2") (pinfunction "2_2") (pintype "passive"))
      (node (ref "C115") (pin "1") (pinfunction "1_1") (pintype "passive"))
      (node (ref "C118") (pin "2") (pinfunction "2_2") (pintype "passive"))
      (node (ref "C119") (pin "1") (pinfunction "1_1") (pintype "passive"))
      (node (ref "C120") (pin "2") (pinfunction "2_2") (pintype "passive"))
      (node (ref "C121") (pin "1") (pinfunction "1_1") (pintype "passive"))
      (node (ref "C122") (pin "2") (pinfunction "2_2") (pintype "passive"))
      (node (ref "C37") (pin "1") (pinfunction "1_1") (pintype "passive"))
      (node (ref "C38") (pin "2") (pinfunction "2_2") (pintype "passive"))
      (node (ref "C87") (pin "1") (pinfunction "1_1") (pintype "passive"))
      (node (ref "C88") (pin "1") (pinfunction "1_1") (pintype "passive"))
      (node (ref "C89") (pin "1") (pinfunction "1_1") (pintype "passive"))
      (node (ref "C90") (pin "1") (pinfunction "1_1") (pintype "passive"))
      (node (ref "C91") (pin "1") (pinfunction "1_1") (pintype "passive"))
      (node (ref "C92") (pin "2") (pinfunction "2_2") (pintype "passive"))
      (node (ref "C93") (pin "2") (pinfunction "2_2") (pintype "passive"))
      (node (ref "C94") (pin "2") (pinfunction "2_2") (pintype "passive"))
      (node (ref "C95") (pin "2") (pinfunction "2_2") (pintype "passive"))
      (node (ref "C96") (pin "2") (pinfunction "2_2") (pintype "passive"))
      (node (ref "C97") (pin "2") (pinfunction "2_2") (pintype "passive"))
      (node (ref "C98") (pin "1") (pinfunction "1_1") (pintype "passive"))
      (node (ref "C99") (pin "1") (pinfunction "1_1") (pintype "passive"))
      (node (ref "DA5") (pin "3") (pinfunction "+_3") (pintype "passive"))
      (node (ref "DA5") (pin "5") (pinfunction "+_5") (pintype "passive"))
      (node (ref "DD3") (pin "1") (pinfunction "NC_1") (pintype "passive"))
      (node (ref "DD3") (pin "10") (pinfunction "TESTIN3_10") (pintype "passive"))
      (node (ref "DD3") (pin "11") (pinfunction "TESTIN4_11") (pintype "passive"))
      (node (ref "DD3") (pin "12") (pinfunction "NC_12") (pintype "passive"))
      (node (ref "DD3") (pin "13") (pinfunction "TESTIN5_13") (pintype "passive"))
      (node (ref "DD3") (pin "14") (pinfunction "TESTIN6_14") (pintype "passive"))
      (node (ref "DD3") (pin "15") (pinfunction "TEST_15") (pintype "passive"))
      (node (ref "DD3") (pin "18") (pinfunction "DVSS_18") (pintype "passive"))
      (node (ref "DD3") (pin "21") (pinfunction "PW0_21") (pintype "passive"))
      (node (ref "DD3") (pin "22") (pinfunction "PW1_22") (pintype "passive"))
      (node (ref "DD3") (pin "23") (pinfunction "PW2_23") (pintype "passive"))
      (node (ref "DD3") (pin "24") (pinfunction "MSN_24") (pintype "passive"))
      (node (ref "DD3") (pin "49") (pinfunction "EPAD_49") (pintype "passive"))
      (node (ref "DD3") (pin "7") (pinfunction "AVSS_7") (pintype "passive"))
      (node (ref "DD3") (pin "8") (pinfunction "TESTIN1_8") (pintype "passive"))
      (node (ref "DD3") (pin "9") (pinfunction "TESTIN2_9") (pintype "passive"))
      (node (ref "R100") (pin "2") (pinfunction "2_2") (pintype "passive"))
      (node (ref "R110") (pin "2") (pinfunction "2_2") (pintype "passive"))
      (node (ref "R113") (pin "2") (pinfunction "2_2") (pintype "passive"))
      (node (ref "R114") (pin "2") (pinfunction "2_2") (pintype "passive"))
      (node (ref "R115") (pin "1") (pinfunction "1_1") (pintype "passive"))
      (node (ref "R116") (pin "1") (pinfunction "1_1") (pintype "passive"))
      (node (ref "R119") (pin "1") (pinfunction "1_1") (pintype "passive"))
      (node (ref "R58") (pin "2") (pinfunction "2_2") (pintype "passive"))
      (node (ref "R62") (pin "2") (pinfunction "2_2") (pintype "passive"))
      (node (ref "R63") (pin "2") (pinfunction "2_2") (pintype "passive"))
      (node (ref "R64") (pin "2") (pinfunction "2_2") (pintype "passive"))
      (node (ref "R66") (pin "1") (pinfunction "1_1") (pintype "passive"))
      (node (ref "R67") (pin "2") (pinfunction "2_2") (pintype "passive"))
      (node (ref "R69") (pin "2") (pinfunction "2_2") (pintype "passive"))
      (node (ref "R78") (pin "1") (pinfunction "1_1") (pintype "passive"))
    )
    (net (code "18") (name "Net-(C86-Pad2)") (class "Default")
      (node (ref "C86") (pin "2") (pinfunction "2_2") (pintype "passive"))
      (node (ref "R55") (pin "2") (pinfunction "2_2") (pintype "passive"))
    )
    (net (code "19") (name "Net-(C102-Pad2)") (class "Default")
      (node (ref "C102") (pin "2") (pinfunction "2_2") (pintype "passive"))
      (node (ref "R61") (pin "2") (pinfunction "2_2") (pintype "passive"))
    )
    (net (code "20") (name "Net-(C109-Pad2)") (class "Default")
      (node (ref "C109") (pin "2") (pinfunction "2_2") (pintype "passive"))
      (node (ref "R72") (pin "2") (pinfunction "2_2") (pintype "passive"))
    )
    (net (code "21") (name "Net-(C117-Pad2)") (class "Default")
      (node (ref "C117") (pin "2") (pinfunction "2_2") (pintype "passive"))
      (node (ref "R77") (pin "2") (pinfunction "2_2") (pintype "passive"))
    )
    (net (code "22") (name "Net-(DA3A--)") (class "Default")
      (node (ref "C101") (pin "2") (pinfunction "2_2") (pintype "passive"))
      (node (ref "DA3") (pin "2") (pinfunction "-_2") (pintype "passive"))
      (node (ref "R60") (pin "2") (pinfunction "2_2") (pintype "passive"))
      (node (ref "R61") (pin "1") (pinfunction "1_1") (pintype "passive"))
    )
    (net (code "23") (name "Net-(DA3A-Out)") (class "Default")
      (node (ref "C101") (pin "1") (pinfunction "1_1") (pintype "passive"))
      (node (ref "DA3") (pin "1") (pinfunction "Out_1") (pintype "passive"))
      (node (ref "R65") (pin "2") (pinfunction "2_2") (pintype "passive"))
    )
    (net (code "24") (name "Net-(DA3B--)") (class "Default")
      (node (ref "C85") (pin "2") (pinfunction "2_2") (pintype "passive"))
      (node (ref "DA3") (pin "6") (pinfunction "-_6") (pintype "passive"))
      (node (ref "R50") (pin "2") (pinfunction "2_2") (pintype "passive"))
      (node (ref "R55") (pin "1") (pinfunction "1_1") (pintype "passive"))
    )
    (net (code "25") (name "Net-(DA3B-Out)") (class "Default")
      (node (ref "C85") (pin "1") (pinfunction "1_1") (pintype "passive"))
      (node (ref "DA3") (pin "7") (pinfunction "Out_7") (pintype "passive"))
      (node (ref "R57") (pin "2") (pinfunction "2_2") (pintype "passive"))
    )
    (net (code "26") (name "Net-(DA4A--)") (class "Default")
      (node (ref "C116") (pin "2") (pinfunction "2_2") (pintype "passive"))
      (node (ref "DA4") (pin "2") (pinfunction "-_2") (pintype "passive"))
      (node (ref "R74") (pin "2") (pinfunction "2_2") (pintype "passive"))
      (node (ref "R77") (pin "1") (pinfunction "1_1") (pintype "passive"))
    )
    (net (code "27") (name "Net-(DA4A-Out)") (class "Default")
      (node (ref "C116") (pin "1") (pinfunction "1_1") (pintype "passive"))
      (node (ref "DA4") (pin "1") (pinfunction "Out_1") (pintype "passive"))
      (node (ref "R79") (pin "2") (pinfunction "2_2") (pintype "passive"))
    )
    (net (code "28") (name "Net-(DA4B--)") (class "Default")
      (node (ref "C108") (pin "2") (pinfunction "2_2") (pintype "passive"))
      (node (ref "DA4") (pin "6") (pinfunction "-_6") (pintype "passive"))
      (node (ref "R70") (pin "2") (pinfunction "2_2") (pintype "passive"))
      (node (ref "R72") (pin "1") (pinfunction "1_1") (pintype "passive"))
    )
    (net (code "29") (name "Net-(DA4B-Out)") (class "Default")
      (node (ref "C108") (pin "1") (pinfunction "1_1") (pintype "passive"))
      (node (ref "DA4") (pin "7") (pinfunction "Out_7") (pintype "passive"))
      (node (ref "R73") (pin "2") (pinfunction "2_2") (pintype "passive"))
    )
    (net (code "30") (name "Net-(DA5A--)") (class "Default")
      (node (ref "DA5") (pin "2") (pinfunction "-_2") (pintype "passive"))
      (node (ref "R51") (pin "2") (pinfunction "2_2") (pintype "passive"))
      (node (ref "R53") (pin "1") (pinfunction "1_1") (pintype "passive"))
    )
    (net (code "31") (name "Net-(DA5A-Out)") (class "Default")
      (node (ref "C102") (pin "1") (pinfunction "1_1") (pintype "passive"))
      (node (ref "DA5") (pin "1") (pinfunction "Out_1") (pintype "passive"))
      (node (ref "R51") (pin "1") (pinfunction "1_1") (pintype "passive"))
    )
    (net (code "32") (name "Net-(DA5B--)") (class "Default")
      (node (ref "DA5") (pin "6") (pinfunction "-_6") (pintype "passive"))
      (node (ref "R75") (pin "2") (pinfunction "2_2") (pintype "passive"))
      (node (ref "R76") (pin "1") (pinfunction "1_1") (pintype "passive"))
    )
    (net (code "33") (name "Net-(DA5B-Out)") (class "Default")
      (node (ref "C109") (pin "1") (pinfunction "1_1") (pintype "passive"))
      (node (ref "DA5") (pin "7") (pinfunction "Out_7") (pintype "passive"))
      (node (ref "R75") (pin "1") (pinfunction "1_1") (pintype "passive"))
    )
    (net (code "34") (name "Net-(DD3-AIN1N)") (class "Default")
      (node (ref "C103") (pin "2") (pinfunction "2_2") (pintype "passive"))
      (node (ref "C92") (pin "1") (pinfunction "1_1") (pintype "passive"))
      (node (ref "DD3") (pin "48") (pinfunction "AIN1N_48") (pintype "passive"))
      (node (ref "R50") (pin "1") (pinfunction "1_1") (pintype "passive"))
      (node (ref "R57") (pin "1") (pinfunction "1_1") (pintype "passive"))
    )
    (net (code "35") (name "Net-(DD3-AIN1P)") (class "Default")
      (node (ref "C103") (pin "1") (pinfunction "1_1") (pintype "passive"))
      (node (ref "C104") (pin "1") (pinfunction "1_1") (pintype "passive"))
      (node (ref "DD3") (pin "47") (pinfunction "AIN1P_47") (pintype "passive"))
      (node (ref "R60") (pin "1") (pinfunction "1_1") (pintype "passive"))
      (node (ref "R65") (pin "1") (pinfunction "1_1") (pintype "passive"))
    )
    (net (code "36") (name "Net-(DD3-AIN2N)") (class "Default")
      (node (ref "C110") (pin "1") (pinfunction "1_1") (pintype "passive"))
      (node (ref "C118") (pin "1") (pinfunction "1_1") (pintype "passive"))
      (node (ref "DD3") (pin "4") (pinfunction "AIN2N_4") (pintype "passive"))
      (node (ref "R74") (pin "1") (pinfunction "1_1") (pintype "passive"))
      (node (ref "R79") (pin "1") (pinfunction "1_1") (pintype "passive"))
    )
    (net (code "37") (name "Net-(DD3-AIN2P)") (class "Default")
      (node (ref "C110") (pin "2") (pinfunction "2_2") (pintype "passive"))
      (node (ref "C114") (pin "1") (pinfunction "1_1") (pintype "passive"))
      (node (ref "DD3") (pin "5") (pinfunction "AIN2P_5") (pintype "passive"))
      (node (ref "R70") (pin "1") (pinfunction "1_1") (pintype "passive"))
      (node (ref "R73") (pin "1") (pinfunction "1_1") (pintype "passive"))
    )
    (net (code "38") (name "Net-(DD3-CKS1{slash}CAD0_I2C{slash}CSN)") (class "Default")
      (node (ref "DD3") (pin "32") (pinfunction "CKS1/CAD0_I2C/CSN_32") (pintype "passive"))
      (node (ref "R118") (pin "2") (pinfunction "2_2") (pintype "passive"))
    )
    (net (code "39") (name "Net-(DD3-CKS3{slash}CAD1)") (class "Default")
      (node (ref "DD3") (pin "34") (pinfunction "CKS3/CAD1_34") (pintype "passive"))
      (node (ref "R117") (pin "2") (pinfunction "2_2") (pintype "passive"))
    )
    (net (code "40") (name "Net-(DD3-DIF0{slash}DSDSEL0)") (class "Default")
      (node (ref "DD3") (pin "37") (pinfunction "DIF0/DSDSEL0_37") (pintype "passive"))
      (node (ref "R64") (pin "1") (pinfunction "1_1") (pintype "passive"))
    )
    (net (code "41") (name "Net-(DD3-DIF1{slash}DSDSEL1)") (class "Default")
      (node (ref "DD3") (pin "38") (pinfunction "DIF1/DSDSEL1_38") (pintype "passive"))
      (node (ref "R63") (pin "1") (pinfunction "1_1") (pintype "passive"))
    )
    (net (code "42") (name "Net-(DD3-DP)") (class "Default")
      (node (ref "DD3") (pin "43") (pinfunction "DP_43") (pintype "passive"))
      (node (ref "R100") (pin "1") (pinfunction "1_1") (pintype "passive"))
    )
    (net (code "43") (name "Net-(DD3-HPFE{slash}DCKS)") (class "Default")
      (node (ref "DD3") (pin "44") (pinfunction "HPFE/DCKS_44") (pintype "passive"))
      (node (ref "R62") (pin "1") (pinfunction "1_1") (pintype "passive"))
    )
    (net (code "44") (name "Net-(DD3-I2C)") (class "Default")
      (node (ref "DD3") (pin "42") (pinfunction "I2C_42") (pintype "passive"))
      (node (ref "R104") (pin "1") (pinfunction "1_1") (pintype "passive"))
    )
    (net (code "45") (name "Net-(DD3-LDOE)") (class "Default")
      (node (ref "DD3") (pin "45") (pinfunction "LDOE_45") (pintype "passive"))
      (node (ref "R94") (pin "1") (pinfunction "1_1") (pintype "passive"))
    )
    (net (code "46") (name "Net-(DD3-ODP)") (class "Default")
      (node (ref "DD3") (pin "46") (pinfunction "ODP_46") (pintype "passive"))
      (node (ref "R67") (pin "1") (pinfunction "1_1") (pintype "passive"))
    )
    (net (code "47") (name "Net-(DD3-PDN)") (class "Default")
      (node (ref "DD3") (pin "20") (pinfunction "PDN_20") (pintype "passive"))
      (node (ref "R80") (pin "2") (pinfunction "2_2") (pintype "passive"))
    )
    (net (code "48") (name "Net-(DD3-PSN{slash}CAD0_SPI)") (class "Default")
      (node (ref "DD3") (pin "41") (pinfunction "PSN/CAD0_SPI_41") (pintype "passive"))
      (node (ref "R110") (pin "1") (pinfunction "1_1") (pintype "passive"))
    )
    (net (code "49") (name "Net-(DD3-SD{slash}PMOD)") (class "Default")
      (node (ref "DD3") (pin "36") (pinfunction "SD/PMOD_36") (pintype "passive"))
      (node (ref "R115") (pin "2") (pinfunction "2_2") (pintype "passive"))
    )
    (net (code "50") (name "Net-(DD3-SLOW{slash}DCKB)") (class "Default")
      (node (ref "DD3") (pin "35") (pinfunction "SLOW/DCKB_35") (pintype "passive"))
      (node (ref "R116") (pin "2") (pinfunction "2_2") (pintype "passive"))
    )
    (net (code "51") (name "Net-(DD3-TDM0)") (class "Default")
      (node (ref "DD3") (pin "39") (pinfunction "TDM0_39") (pintype "passive"))
      (node (ref "R114") (pin "1") (pinfunction "1_1") (pintype "passive"))
    )
    (net (code "52") (name "Net-(DD3-TDM1)") (class "Default")
      (node (ref "DD3") (pin "40") (pinfunction "TDM1_40") (pintype "passive"))
      (node (ref "R113") (pin "1") (pinfunction "1_1") (pintype "passive"))
    )
    (net (code "53") (name "Net-(DD3-TDMIN{slash}DSDOR1)") (class "Default")
      (node (ref "DD3") (pin "27") (pinfunction "TDMIN/DSDOR1_27") (pintype "passive"))
      (node (ref "R119") (pin "2") (pinfunction "2_2") (pintype "passive"))
    )
    (net (code "54") (name "Net-(DD3-VDD18)") (class "Default")
      (node (ref "C120") (pin "1") (pinfunction "1_1") (pintype "passive"))
      (node (ref "C122") (pin "1") (pinfunction "1_1") (pintype "passive"))
      (node (ref "DD3") (pin "19") (pinfunction "VDD18_19") (pintype "passive"))
    )
    (net (code "55") (name "Net-(DD3-VREFH1)") (class "Default")
      (node (ref "C105") (pin "2") (pinfunction "2_2") (pintype "passive"))
      (node (ref "C107") (pin "1") (pinfunction "1_1") (pintype "passive"))
      (node (ref "C35") (pin "1") (pinfunction "1_1") (pintype "passive"))
      (node (ref "DD3") (pin "3") (pinfunction "VREFH1_3") (pintype "passive"))
      (node (ref "R71") (pin "1") (pinfunction "1_1") (pintype "passive"))
    )
    (net (code "56") (name "Net-(DD3-VREFL1)") (class "Default")
      (node (ref "C105") (pin "1") (pinfunction "1_1") (pintype "passive"))
      (node (ref "C107") (pin "2") (pinfunction "2_2") (pintype "passive"))
      (node (ref "C35") (pin "2") (pinfunction "2_2") (pintype "passive"))
      (node (ref "DD3") (pin "2") (pinfunction "VREFL1_2") (pintype "passive"))
      (node (ref "R69") (pin "1") (pinfunction "1_1") (pintype "passive"))
    )
    (net (code "57") (name "Net-(R56-Pad1)") (class "Default")
      (node (ref "R56") (pin "1") (pinfunction "1_1") (pintype "passive"))
      (node (ref "R58") (pin "1") (pinfunction "1_1") (pintype "passive"))
    )
    (net (code "58") (name "unconnected-(DD3-OVF-Pad30)") (class "Default")
      (node (ref "DD3") (pin "30") (pinfunction "OVF_30") (pintype "passive+no_connect"))
    )
    (net (code "59") (name "unconnected-(DD3-TESTO1-Pad29)") (class "Default")
      (node (ref "DD3") (pin "29") (pinfunction "TESTO1_29") (pintype "passive+no_connect"))
    )
  )
)
